# LED_addon_v6.net
KiCad netlist of a schematic drawn in EAGLE
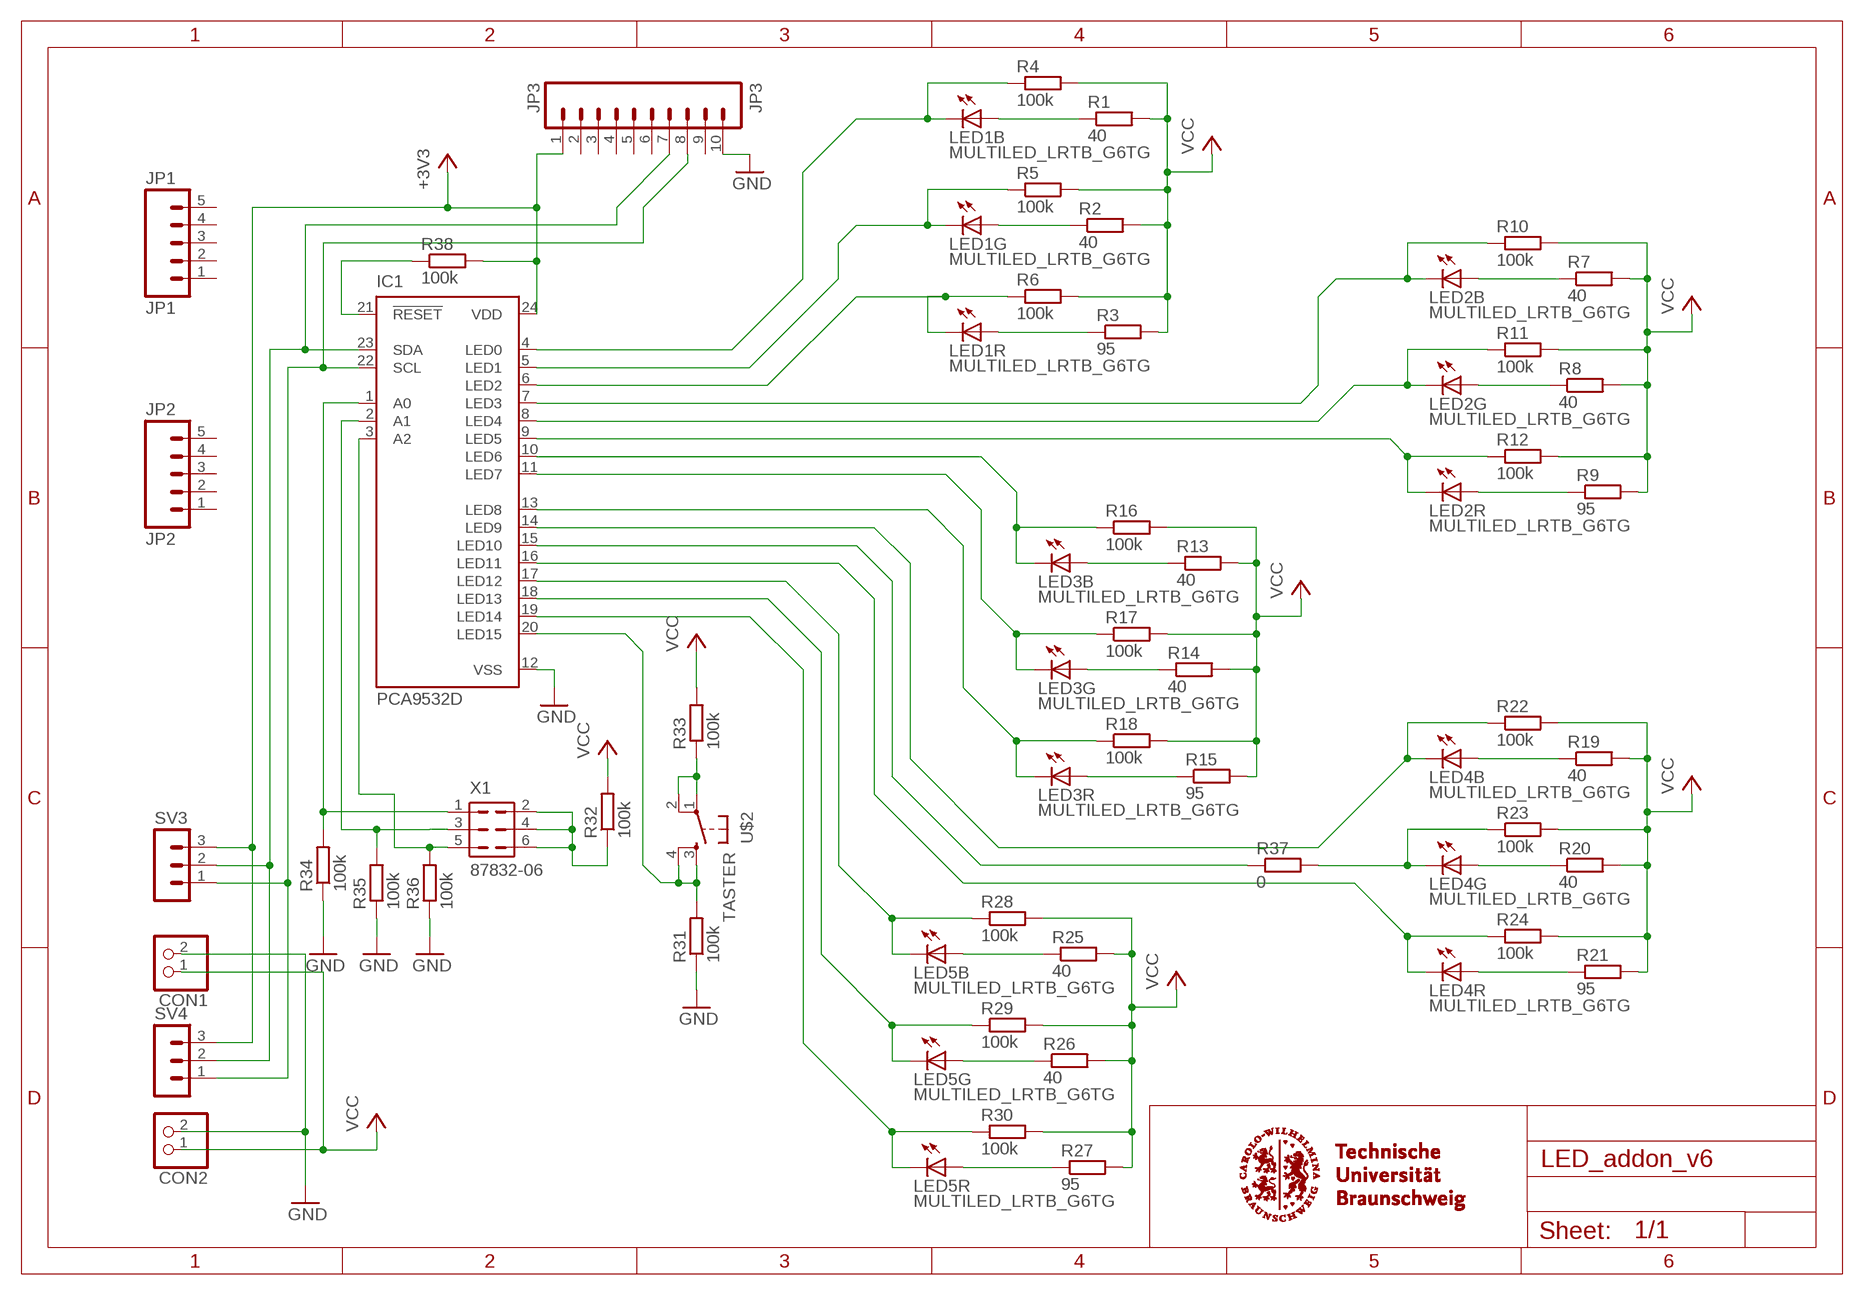
[diagram p0: schematic, sheet 1]

(export (version "E")
  (design (tool "Eeschema 10.0.6"))
  (components
    (comp (ref "CON1")
      (value "PINHD-1X2")
      (footprint "eagle-import:1X02")
      (libsource (lib "eagle-import") (part "PINHD-1X2"))
    )
    (comp (ref "CON2")
      (value "PINHD-1X2")
      (footprint "eagle-import:1X02")
      (libsource (lib "eagle-import") (part "PINHD-1X2"))
    )
    (comp (ref "IC1")
      (value "PCA9532D")
      (footprint "eagle-import:SO24")
      (libsource (lib "eagle-import") (part "PCA9532D"))
    )
    (comp (ref "JP1")
      (value "JP1")
      (footprint "eagle-import:1X05")
      (libsource (lib "eagle-import") (part "M05PTH"))
    )
    (comp (ref "JP2")
      (value "JP2")
      (footprint "eagle-import:1X05")
      (libsource (lib "eagle-import") (part "M05PTH"))
    )
    (comp (ref "JP3")
      (value "JP3")
      (footprint "eagle-import:1X10")
      (libsource (lib "eagle-import") (part "M10{dblquote}"))
    )
    (comp (ref "LED1")
      (value "MULTILED_LRTB_G6TG")
      (footprint "eagle-import:P-LCC-6_TOPLED")
      (libsource (lib "eagle-import") (part "MULTILED_LRTB_G6TG"))
    )
    (comp (ref "LED2")
      (value "MULTILED_LRTB_G6TG")
      (footprint "eagle-import:P-LCC-6_TOPLED")
      (libsource (lib "eagle-import") (part "MULTILED_LRTB_G6TG"))
    )
    (comp (ref "LED3")
      (value "MULTILED_LRTB_G6TG")
      (footprint "eagle-import:P-LCC-6_TOPLED")
      (libsource (lib "eagle-import") (part "MULTILED_LRTB_G6TG"))
    )
    (comp (ref "LED4")
      (value "MULTILED_LRTB_G6TG")
      (footprint "eagle-import:P-LCC-6_TOPLED")
      (libsource (lib "eagle-import") (part "MULTILED_LRTB_G6TG"))
    )
    (comp (ref "LED5")
      (value "MULTILED_LRTB_G6TG")
      (footprint "eagle-import:P-LCC-6_TOPLED")
      (libsource (lib "eagle-import") (part "MULTILED_LRTB_G6TG"))
    )
    (comp (ref "R1")
      (value "40")
      (footprint "eagle-import:M0805")
      (libsource (lib "eagle-import") (part "R-EU_M0805"))
    )
    (comp (ref "R2")
      (value "40")
      (footprint "eagle-import:M0805")
      (libsource (lib "eagle-import") (part "R-EU_M0805"))
    )
    (comp (ref "R3")
      (value "95")
      (footprint "eagle-import:M0805")
      (libsource (lib "eagle-import") (part "R-EU_M0805"))
    )
    (comp (ref "R4")
      (value "100k")
      (footprint "eagle-import:M0805")
      (libsource (lib "eagle-import") (part "R-EU_M0805"))
    )
    (comp (ref "R5")
      (value "100k")
      (footprint "eagle-import:M0805")
      (libsource (lib "eagle-import") (part "R-EU_M0805"))
    )
    (comp (ref "R6")
      (value "100k")
      (footprint "eagle-import:M0805")
      (libsource (lib "eagle-import") (part "R-EU_M0805"))
    )
    (comp (ref "R7")
      (value "40")
      (footprint "eagle-import:M0805")
      (libsource (lib "eagle-import") (part "R-EU_M0805"))
    )
    (comp (ref "R8")
      (value "40")
      (footprint "eagle-import:M0805")
      (libsource (lib "eagle-import") (part "R-EU_M0805"))
    )
    (comp (ref "R9")
      (value "95")
      (footprint "eagle-import:M0805")
      (libsource (lib "eagle-import") (part "R-EU_M0805"))
    )
    (comp (ref "R10")
      (value "100k")
      (footprint "eagle-import:M0805")
      (libsource (lib "eagle-import") (part "R-EU_M0805"))
    )
    (comp (ref "R11")
      (value "100k")
      (footprint "eagle-import:M0805")
      (libsource (lib "eagle-import") (part "R-EU_M0805"))
    )
    (comp (ref "R12")
      (value "100k")
      (footprint "eagle-import:M0805")
      (libsource (lib "eagle-import") (part "R-EU_M0805"))
    )
    (comp (ref "R13")
      (value "40")
      (footprint "eagle-import:M0805")
      (libsource (lib "eagle-import") (part "R-EU_M0805"))
    )
    (comp (ref "R14")
      (value "40")
      (footprint "eagle-import:M0805")
      (libsource (lib "eagle-import") (part "R-EU_M0805"))
    )
    (comp (ref "R15")
      (value "95")
      (footprint "eagle-import:M0805")
      (libsource (lib "eagle-import") (part "R-EU_M0805"))
    )
    (comp (ref "R16")
      (value "100k")
      (footprint "eagle-import:M0805")
      (libsource (lib "eagle-import") (part "R-EU_M0805"))
    )
    (comp (ref "R17")
      (value "100k")
      (footprint "eagle-import:M0805")
      (libsource (lib "eagle-import") (part "R-EU_M0805"))
    )
    (comp (ref "R18")
      (value "100k")
      (footprint "eagle-import:M0805")
      (libsource (lib "eagle-import") (part "R-EU_M0805"))
    )
    (comp (ref "R19")
      (value "40")
      (footprint "eagle-import:M0805")
      (libsource (lib "eagle-import") (part "R-EU_M0805"))
    )
    (comp (ref "R20")
      (value "40")
      (footprint "eagle-import:M0805")
      (libsource (lib "eagle-import") (part "R-EU_M0805"))
    )
    (comp (ref "R21")
      (value "95")
      (footprint "eagle-import:M0805")
      (libsource (lib "eagle-import") (part "R-EU_M0805"))
    )
    (comp (ref "R22")
      (value "100k")
      (footprint "eagle-import:M0805")
      (libsource (lib "eagle-import") (part "R-EU_M0805"))
    )
    (comp (ref "R23")
      (value "100k")
      (footprint "eagle-import:M0805")
      (libsource (lib "eagle-import") (part "R-EU_M0805"))
    )
    (comp (ref "R24")
      (value "100k")
      (footprint "eagle-import:M0805")
      (libsource (lib "eagle-import") (part "R-EU_M0805"))
    )
    (comp (ref "R25")
      (value "40")
      (footprint "eagle-import:M0805")
      (libsource (lib "eagle-import") (part "R-EU_M0805"))
    )
    (comp (ref "R26")
      (value "40")
      (footprint "eagle-import:M0805")
      (libsource (lib "eagle-import") (part "R-EU_M0805"))
    )
    (comp (ref "R27")
      (value "95")
      (footprint "eagle-import:M0805")
      (libsource (lib "eagle-import") (part "R-EU_M0805"))
    )
    (comp (ref "R28")
      (value "100k")
      (footprint "eagle-import:M0805")
      (libsource (lib "eagle-import") (part "R-EU_M0805"))
    )
    (comp (ref "R29")
      (value "100k")
      (footprint "eagle-import:M0805")
      (libsource (lib "eagle-import") (part "R-EU_M0805"))
    )
    (comp (ref "R30")
      (value "100k")
      (footprint "eagle-import:R0603")
      (libsource (lib "eagle-import") (part "R-EU_R0603"))
    )
    (comp (ref "R31")
      (value "100k")
      (footprint "eagle-import:M0805")
      (libsource (lib "eagle-import") (part "R-EU_M0805"))
    )
    (comp (ref "R32")
      (value "100k")
      (footprint "eagle-import:M0805")
      (libsource (lib "eagle-import") (part "R-EU_M0805"))
    )
    (comp (ref "R33")
      (value "100k")
      (footprint "eagle-import:M0805")
      (libsource (lib "eagle-import") (part "R-EU_M0805"))
    )
    (comp (ref "R34")
      (value "100k")
      (footprint "eagle-import:M0805")
      (libsource (lib "eagle-import") (part "R-EU_M0805"))
    )
    (comp (ref "R35")
      (value "100k")
      (footprint "eagle-import:M0805")
      (libsource (lib "eagle-import") (part "R-EU_M0805"))
    )
    (comp (ref "R36")
      (value "100k")
      (footprint "eagle-import:M0805")
      (libsource (lib "eagle-import") (part "R-EU_M0805"))
    )
    (comp (ref "R37")
      (value "0")
      (footprint "eagle-import:M1206")
      (libsource (lib "eagle-import") (part "R-EU_M1206"))
    )
    (comp (ref "R38")
      (value "100k")
      (footprint "eagle-import:M0805")
      (libsource (lib "eagle-import") (part "R-EU_M0805"))
    )
    (comp (ref "SV3")
      (value "MA03-1")
      (footprint "eagle-import:MA03-1")
      (libsource (lib "eagle-import") (part "MA03-1"))
    )
    (comp (ref "SV4")
      (value "MA03-1")
      (footprint "eagle-import:MA03-1")
      (libsource (lib "eagle-import") (part "MA03-1"))
    )
    (comp (ref "U$2")
      (value "TASTER")
      (footprint "eagle-import:TASTER")
      (libsource (lib "eagle-import") (part "TASTER"))
    )
    (comp (ref "X1")
      (value "87832-06")
      (footprint "eagle-import:87832-06")
      (libsource (lib "eagle-import") (part "87832-06"))
    )
  )
  (nets
    (net (code "1") (name "+3V3") (class "Default")
      (node (ref "IC1") (pin "24") (pinfunction "VDD_24") (pintype "power_in"))
      (node (ref "JP3") (pin "1") (pinfunction "1_1") (pintype "passive"))
      (node (ref "R38") (pin "2") (pinfunction "2_2") (pintype "passive"))
      (node (ref "SV3") (pin "3") (pinfunction "3_3") (pintype "passive"))
      (node (ref "SV4") (pin "3") (pinfunction "3_3") (pintype "passive"))
    )
    (net (code "2") (name "GND") (class "Default")
      (node (ref "CON1") (pin "2") (pinfunction "2_2") (pintype "passive"))
      (node (ref "CON2") (pin "2") (pinfunction "2_2") (pintype "passive"))
      (node (ref "IC1") (pin "12") (pinfunction "VSS_12") (pintype "power_in"))
      (node (ref "JP3") (pin "10") (pinfunction "10_10") (pintype "passive"))
      (node (ref "R31") (pin "1") (pinfunction "1_1") (pintype "passive"))
      (node (ref "R34") (pin "1") (pinfunction "1_1") (pintype "passive"))
      (node (ref "R35") (pin "1") (pinfunction "1_1") (pintype "passive"))
      (node (ref "R36") (pin "1") (pinfunction "1_1") (pintype "passive"))
    )
    (net (code "3") (name "Net-(IC1-A0)") (class "Default")
      (node (ref "IC1") (pin "1") (pinfunction "A0_1") (pintype "input"))
      (node (ref "R34") (pin "2") (pinfunction "2_2") (pintype "passive"))
      (node (ref "X1") (pin "1") (pinfunction "1_1") (pintype "passive"))
    )
    (net (code "4") (name "Net-(IC1-A1)") (class "Default")
      (node (ref "IC1") (pin "2") (pinfunction "A1_2") (pintype "input"))
      (node (ref "R35") (pin "2") (pinfunction "2_2") (pintype "passive"))
      (node (ref "X1") (pin "3") (pinfunction "3_3") (pintype "passive"))
    )
    (net (code "5") (name "Net-(IC1-A2)") (class "Default")
      (node (ref "IC1") (pin "3") (pinfunction "A2_3") (pintype "input"))
      (node (ref "R36") (pin "2") (pinfunction "2_2") (pintype "passive"))
      (node (ref "X1") (pin "5") (pinfunction "5_5") (pintype "passive"))
    )
    (net (code "6") (name "Net-(IC1-LED0)") (class "Default")
      (node (ref "IC1") (pin "4") (pinfunction "LED0_4") (pintype "bidirectional"))
      (node (ref "LED1") (pin "C3") (pinfunction "C_C3") (pintype "passive"))
      (node (ref "R4") (pin "1") (pinfunction "1_1") (pintype "passive"))
    )
    (net (code "7") (name "Net-(IC1-LED1)") (class "Default")
      (node (ref "IC1") (pin "5") (pinfunction "LED1_5") (pintype "bidirectional"))
      (node (ref "LED1") (pin "C2") (pinfunction "C_C2") (pintype "passive"))
      (node (ref "R5") (pin "1") (pinfunction "1_1") (pintype "passive"))
    )
    (net (code "8") (name "Net-(IC1-LED2)") (class "Default")
      (node (ref "IC1") (pin "6") (pinfunction "LED2_6") (pintype "bidirectional"))
      (node (ref "LED1") (pin "C1") (pinfunction "C_C1") (pintype "passive"))
      (node (ref "R6") (pin "1") (pinfunction "1_1") (pintype "passive"))
    )
    (net (code "9") (name "Net-(IC1-LED3)") (class "Default")
      (node (ref "IC1") (pin "7") (pinfunction "LED3_7") (pintype "bidirectional"))
      (node (ref "LED2") (pin "C3") (pinfunction "C_C3") (pintype "passive"))
      (node (ref "R10") (pin "1") (pinfunction "1_1") (pintype "passive"))
    )
    (net (code "10") (name "Net-(IC1-LED4)") (class "Default")
      (node (ref "IC1") (pin "8") (pinfunction "LED4_8") (pintype "bidirectional"))
      (node (ref "LED2") (pin "C2") (pinfunction "C_C2") (pintype "passive"))
      (node (ref "R11") (pin "1") (pinfunction "1_1") (pintype "passive"))
    )
    (net (code "11") (name "Net-(IC1-LED5)") (class "Default")
      (node (ref "IC1") (pin "9") (pinfunction "LED5_9") (pintype "bidirectional"))
      (node (ref "LED2") (pin "C1") (pinfunction "C_C1") (pintype "passive"))
      (node (ref "R12") (pin "1") (pinfunction "1_1") (pintype "passive"))
    )
    (net (code "12") (name "Net-(IC1-LED6)") (class "Default")
      (node (ref "IC1") (pin "10") (pinfunction "LED6_10") (pintype "bidirectional"))
      (node (ref "LED3") (pin "C3") (pinfunction "C_C3") (pintype "passive"))
      (node (ref "R16") (pin "1") (pinfunction "1_1") (pintype "passive"))
    )
    (net (code "13") (name "Net-(IC1-LED7)") (class "Default")
      (node (ref "IC1") (pin "11") (pinfunction "LED7_11") (pintype "bidirectional"))
      (node (ref "LED3") (pin "C2") (pinfunction "C_C2") (pintype "passive"))
      (node (ref "R17") (pin "1") (pinfunction "1_1") (pintype "passive"))
    )
    (net (code "14") (name "Net-(IC1-LED8)") (class "Default")
      (node (ref "IC1") (pin "13") (pinfunction "LED8_13") (pintype "bidirectional"))
      (node (ref "LED3") (pin "C1") (pinfunction "C_C1") (pintype "passive"))
      (node (ref "R18") (pin "1") (pinfunction "1_1") (pintype "passive"))
    )
    (net (code "15") (name "Net-(IC1-LED9)") (class "Default")
      (node (ref "IC1") (pin "14") (pinfunction "LED9_14") (pintype "bidirectional"))
      (node (ref "LED4") (pin "C3") (pinfunction "C_C3") (pintype "passive"))
      (node (ref "R22") (pin "1") (pinfunction "1_1") (pintype "passive"))
    )
    (net (code "16") (name "Net-(IC1-LED10)") (class "Default")
      (node (ref "IC1") (pin "15") (pinfunction "LED10_15") (pintype "bidirectional"))
      (node (ref "R37") (pin "1") (pinfunction "1_1") (pintype "passive"))
    )
    (net (code "17") (name "Net-(IC1-LED11)") (class "Default")
      (node (ref "IC1") (pin "16") (pinfunction "LED11_16") (pintype "bidirectional"))
      (node (ref "LED4") (pin "C1") (pinfunction "C_C1") (pintype "passive"))
      (node (ref "R24") (pin "1") (pinfunction "1_1") (pintype "passive"))
    )
    (net (code "18") (name "Net-(IC1-LED12)") (class "Default")
      (node (ref "IC1") (pin "17") (pinfunction "LED12_17") (pintype "bidirectional"))
      (node (ref "LED5") (pin "C3") (pinfunction "C_C3") (pintype "passive"))
      (node (ref "R28") (pin "1") (pinfunction "1_1") (pintype "passive"))
    )
    (net (code "19") (name "Net-(IC1-LED13)") (class "Default")
      (node (ref "IC1") (pin "18") (pinfunction "LED13_18") (pintype "bidirectional"))
      (node (ref "LED5") (pin "C2") (pinfunction "C_C2") (pintype "passive"))
      (node (ref "R29") (pin "1") (pinfunction "1_1") (pintype "passive"))
    )
    (net (code "20") (name "Net-(IC1-LED14)") (class "Default")
      (node (ref "IC1") (pin "19") (pinfunction "LED14_19") (pintype "bidirectional"))
      (node (ref "LED5") (pin "C1") (pinfunction "C_C1") (pintype "passive"))
      (node (ref "R30") (pin "1") (pinfunction "1_1") (pintype "passive"))
    )
    (net (code "21") (name "Net-(IC1-LED15)") (class "Default")
      (node (ref "IC1") (pin "20") (pinfunction "LED15_20") (pintype "bidirectional"))
      (node (ref "R31") (pin "2") (pinfunction "2_2") (pintype "passive"))
      (node (ref "U$2") (pin "3") (pinfunction "S_3") (pintype "passive"))
      (node (ref "U$2") (pin "4") (pinfunction "S1_4") (pintype "passive"))
    )
    (net (code "22") (name "Net-(IC1-SCL)") (class "Default")
      (node (ref "IC1") (pin "22") (pinfunction "SCL_22") (pintype "input"))
      (node (ref "JP3") (pin "8") (pinfunction "8_8") (pintype "passive"))
      (node (ref "SV3") (pin "1") (pinfunction "1_1") (pintype "passive"))
      (node (ref "SV4") (pin "1") (pinfunction "1_1") (pintype "passive"))
    )
    (net (code "23") (name "Net-(IC1-SDA)") (class "Default")
      (node (ref "IC1") (pin "23") (pinfunction "SDA_23") (pintype "bidirectional"))
      (node (ref "JP3") (pin "7") (pinfunction "7_7") (pintype "passive"))
      (node (ref "SV3") (pin "2") (pinfunction "2_2") (pintype "passive"))
      (node (ref "SV4") (pin "2") (pinfunction "2_2") (pintype "passive"))
    )
    (net (code "24") (name "Net-(IC1-~{RESET})") (class "Default")
      (node (ref "IC1") (pin "21") (pinfunction "~{RESET}_21") (pintype "input"))
      (node (ref "R38") (pin "1") (pinfunction "1_1") (pintype "passive"))
    )
    (net (code "25") (name "Net-(LED1A-A)") (class "Default")
      (node (ref "LED1") (pin "A3") (pinfunction "A_A3") (pintype "passive"))
      (node (ref "R1") (pin "1") (pinfunction "1_1") (pintype "passive"))
    )
    (net (code "26") (name "Net-(LED1B-A)") (class "Default")
      (node (ref "LED1") (pin "A2") (pinfunction "A_A2") (pintype "passive"))
      (node (ref "R2") (pin "1") (pinfunction "1_1") (pintype "passive"))
    )
    (net (code "27") (name "Net-(LED1C-A)") (class "Default")
      (node (ref "LED1") (pin "A1") (pinfunction "A_A1") (pintype "passive"))
      (node (ref "R3") (pin "1") (pinfunction "1_1") (pintype "passive"))
    )
    (net (code "28") (name "Net-(LED2A-A)") (class "Default")
      (node (ref "LED2") (pin "A3") (pinfunction "A_A3") (pintype "passive"))
      (node (ref "R7") (pin "1") (pinfunction "1_1") (pintype "passive"))
    )
    (net (code "29") (name "Net-(LED2B-A)") (class "Default")
      (node (ref "LED2") (pin "A2") (pinfunction "A_A2") (pintype "passive"))
      (node (ref "R8") (pin "1") (pinfunction "1_1") (pintype "passive"))
    )
    (net (code "30") (name "Net-(LED2C-A)") (class "Default")
      (node (ref "LED2") (pin "A1") (pinfunction "A_A1") (pintype "passive"))
      (node (ref "R9") (pin "1") (pinfunction "1_1") (pintype "passive"))
    )
    (net (code "31") (name "Net-(LED3A-A)") (class "Default")
      (node (ref "LED3") (pin "A3") (pinfunction "A_A3") (pintype "passive"))
      (node (ref "R13") (pin "1") (pinfunction "1_1") (pintype "passive"))
    )
    (net (code "32") (name "Net-(LED3B-A)") (class "Default")
      (node (ref "LED3") (pin "A2") (pinfunction "A_A2") (pintype "passive"))
      (node (ref "R14") (pin "1") (pinfunction "1_1") (pintype "passive"))
    )
    (net (code "33") (name "Net-(LED3C-A)") (class "Default")
      (node (ref "LED3") (pin "A1") (pinfunction "A_A1") (pintype "passive"))
      (node (ref "R15") (pin "1") (pinfunction "1_1") (pintype "passive"))
    )
    (net (code "34") (name "Net-(LED4A-A)") (class "Default")
      (node (ref "LED4") (pin "A3") (pinfunction "A_A3") (pintype "passive"))
      (node (ref "R19") (pin "1") (pinfunction "1_1") (pintype "passive"))
    )
    (net (code "35") (name "Net-(LED4B-A)") (class "Default")
      (node (ref "LED4") (pin "A2") (pinfunction "A_A2") (pintype "passive"))
      (node (ref "R20") (pin "1") (pinfunction "1_1") (pintype "passive"))
    )
    (net (code "36") (name "Net-(LED4B-C)") (class "Default")
      (node (ref "LED4") (pin "C2") (pinfunction "C_C2") (pintype "passive"))
      (node (ref "R23") (pin "1") (pinfunction "1_1") (pintype "passive"))
      (node (ref "R37") (pin "2") (pinfunction "2_2") (pintype "passive"))
    )
    (net (code "37") (name "Net-(LED4C-A)") (class "Default")
      (node (ref "LED4") (pin "A1") (pinfunction "A_A1") (pintype "passive"))
      (node (ref "R21") (pin "1") (pinfunction "1_1") (pintype "passive"))
    )
    (net (code "38") (name "Net-(LED5A-A)") (class "Default")
      (node (ref "LED5") (pin "A3") (pinfunction "A_A3") (pintype "passive"))
      (node (ref "R25") (pin "1") (pinfunction "1_1") (pintype "passive"))
    )
    (net (code "39") (name "Net-(LED5B-A)") (class "Default")
      (node (ref "LED5") (pin "A2") (pinfunction "A_A2") (pintype "passive"))
      (node (ref "R26") (pin "1") (pinfunction "1_1") (pintype "passive"))
    )
    (net (code "40") (name "Net-(LED5C-A)") (class "Default")
      (node (ref "LED5") (pin "A1") (pinfunction "A_A1") (pintype "passive"))
      (node (ref "R27") (pin "1") (pinfunction "1_1") (pintype "passive"))
    )
    (net (code "41") (name "Net-(R32-Pad1)") (class "Default")
      (node (ref "R32") (pin "1") (pinfunction "1_1") (pintype "passive"))
      (node (ref "X1") (pin "2") (pinfunction "2_2") (pintype "passive"))
      (node (ref "X1") (pin "4") (pinfunction "4_4") (pintype "passive"))
      (node (ref "X1") (pin "6") (pinfunction "6_6") (pintype "passive"))
    )
    (net (code "42") (name "Net-(U$2-P)") (class "Default")
      (node (ref "R33") (pin "1") (pinfunction "1_1") (pintype "passive"))
      (node (ref "U$2") (pin "1") (pinfunction "P_1") (pintype "passive"))
      (node (ref "U$2") (pin "2") (pinfunction "P1_2") (pintype "passive"))
    )
    (net (code "43") (name "VCC") (class "Default")
      (node (ref "CON1") (pin "1") (pinfunction "1_1") (pintype "passive"))
      (node (ref "CON2") (pin "1") (pinfunction "1_1") (pintype "passive"))
      (node (ref "R1") (pin "2") (pinfunction "2_2") (pintype "passive"))
      (node (ref "R10") (pin "2") (pinfunction "2_2") (pintype "passive"))
      (node (ref "R11") (pin "2") (pinfunction "2_2") (pintype "passive"))
      (node (ref "R12") (pin "2") (pinfunction "2_2") (pintype "passive"))
      (node (ref "R13") (pin "2") (pinfunction "2_2") (pintype "passive"))
      (node (ref "R14") (pin "2") (pinfunction "2_2") (pintype "passive"))
      (node (ref "R15") (pin "2") (pinfunction "2_2") (pintype "passive"))
      (node (ref "R16") (pin "2") (pinfunction "2_2") (pintype "passive"))
      (node (ref "R17") (pin "2") (pinfunction "2_2") (pintype "passive"))
      (node (ref "R18") (pin "2") (pinfunction "2_2") (pintype "passive"))
      (node (ref "R19") (pin "2") (pinfunction "2_2") (pintype "passive"))
      (node (ref "R2") (pin "2") (pinfunction "2_2") (pintype "passive"))
      (node (ref "R20") (pin "2") (pinfunction "2_2") (pintype "passive"))
      (node (ref "R21") (pin "2") (pinfunction "2_2") (pintype "passive"))
      (node (ref "R22") (pin "2") (pinfunction "2_2") (pintype "passive"))
      (node (ref "R23") (pin "2") (pinfunction "2_2") (pintype "passive"))
      (node (ref "R24") (pin "2") (pinfunction "2_2") (pintype "passive"))
      (node (ref "R25") (pin "2") (pinfunction "2_2") (pintype "passive"))
      (node (ref "R26") (pin "2") (pinfunction "2_2") (pintype "passive"))
      (node (ref "R27") (pin "2") (pinfunction "2_2") (pintype "passive"))
      (node (ref "R28") (pin "2") (pinfunction "2_2") (pintype "passive"))
      (node (ref "R29") (pin "2") (pinfunction "2_2") (pintype "passive"))
      (node (ref "R3") (pin "2") (pinfunction "2_2") (pintype "passive"))
      (node (ref "R30") (pin "2") (pinfunction "2_2") (pintype "passive"))
      (node (ref "R32") (pin "2") (pinfunction "2_2") (pintype "passive"))
      (node (ref "R33") (pin "2") (pinfunction "2_2") (pintype "passive"))
      (node (ref "R4") (pin "2") (pinfunction "2_2") (pintype "passive"))
      (node (ref "R5") (pin "2") (pinfunction "2_2") (pintype "passive"))
      (node (ref "R6") (pin "2") (pinfunction "2_2") (pintype "passive"))
      (node (ref "R7") (pin "2") (pinfunction "2_2") (pintype "passive"))
      (node (ref "R8") (pin "2") (pinfunction "2_2") (pintype "passive"))
      (node (ref "R9") (pin "2") (pinfunction "2_2") (pintype "passive"))
    )
    (net (code "44") (name "unconnected-(JP1-Pad1)") (class "Default")
      (node (ref "JP1") (pin "1") (pinfunction "1_1") (pintype "passive"))
    )
    (net (code "45") (name "unconnected-(JP1-Pad2)") (class "Default")
      (node (ref "JP1") (pin "2") (pinfunction "2_2") (pintype "passive"))
    )
    (net (code "46") (name "unconnected-(JP1-Pad3)") (class "Default")
      (node (ref "JP1") (pin "3") (pinfunction "3_3") (pintype "passive"))
    )
    (net (code "47") (name "unconnected-(JP1-Pad4)") (class "Default")
      (node (ref "JP1") (pin "4") (pinfunction "4_4") (pintype "passive"))
    )
    (net (code "48") (name "unconnected-(JP1-Pad5)") (class "Default")
      (node (ref "JP1") (pin "5") (pinfunction "5_5") (pintype "passive"))
    )
    (net (code "49") (name "unconnected-(JP2-Pad1)") (class "Default")
      (node (ref "JP2") (pin "1") (pinfunction "1_1") (pintype "passive"))
    )
    (net (code "50") (name "unconnected-(JP2-Pad2)") (class "Default")
      (node (ref "JP2") (pin "2") (pinfunction "2_2") (pintype "passive"))
    )
    (net (code "51") (name "unconnected-(JP2-Pad3)") (class "Default")
      (node (ref "JP2") (pin "3") (pinfunction "3_3") (pintype "passive"))
    )
    (net (code "52") (name "unconnected-(JP2-Pad4)") (class "Default")
      (node (ref "JP2") (pin "4") (pinfunction "4_4") (pintype "passive"))
    )
    (net (code "53") (name "unconnected-(JP2-Pad5)") (class "Default")
      (node (ref "JP2") (pin "5") (pinfunction "5_5") (pintype "passive"))
    )
    (net (code "54") (name "unconnected-(JP3-Pad2)") (class "Default")
      (node (ref "JP3") (pin "2") (pinfunction "2_2") (pintype "passive"))
    )
    (net (code "55") (name "unconnected-(JP3-Pad3)") (class "Default")
      (node (ref "JP3") (pin "3") (pinfunction "3_3") (pintype "passive"))
    )
    (net (code "56") (name "unconnected-(JP3-Pad4)") (class "Default")
      (node (ref "JP3") (pin "4") (pinfunction "4_4") (pintype "passive"))
    )
    (net (code "57") (name "unconnected-(JP3-Pad5)") (class "Default")
      (node (ref "JP3") (pin "5") (pinfunction "5_5") (pintype "passive"))
    )
    (net (code "58") (name "unconnected-(JP3-Pad6)") (class "Default")
      (node (ref "JP3") (pin "6") (pinfunction "6_6") (pintype "passive"))
    )
    (net (code "59") (name "unconnected-(JP3-Pad9)") (class "Default")
      (node (ref "JP3") (pin "9") (pinfunction "9_9") (pintype "passive"))
    )
  )
)
